# schematic.net
KiCad netlist of a schematic drawn in EasyEDA
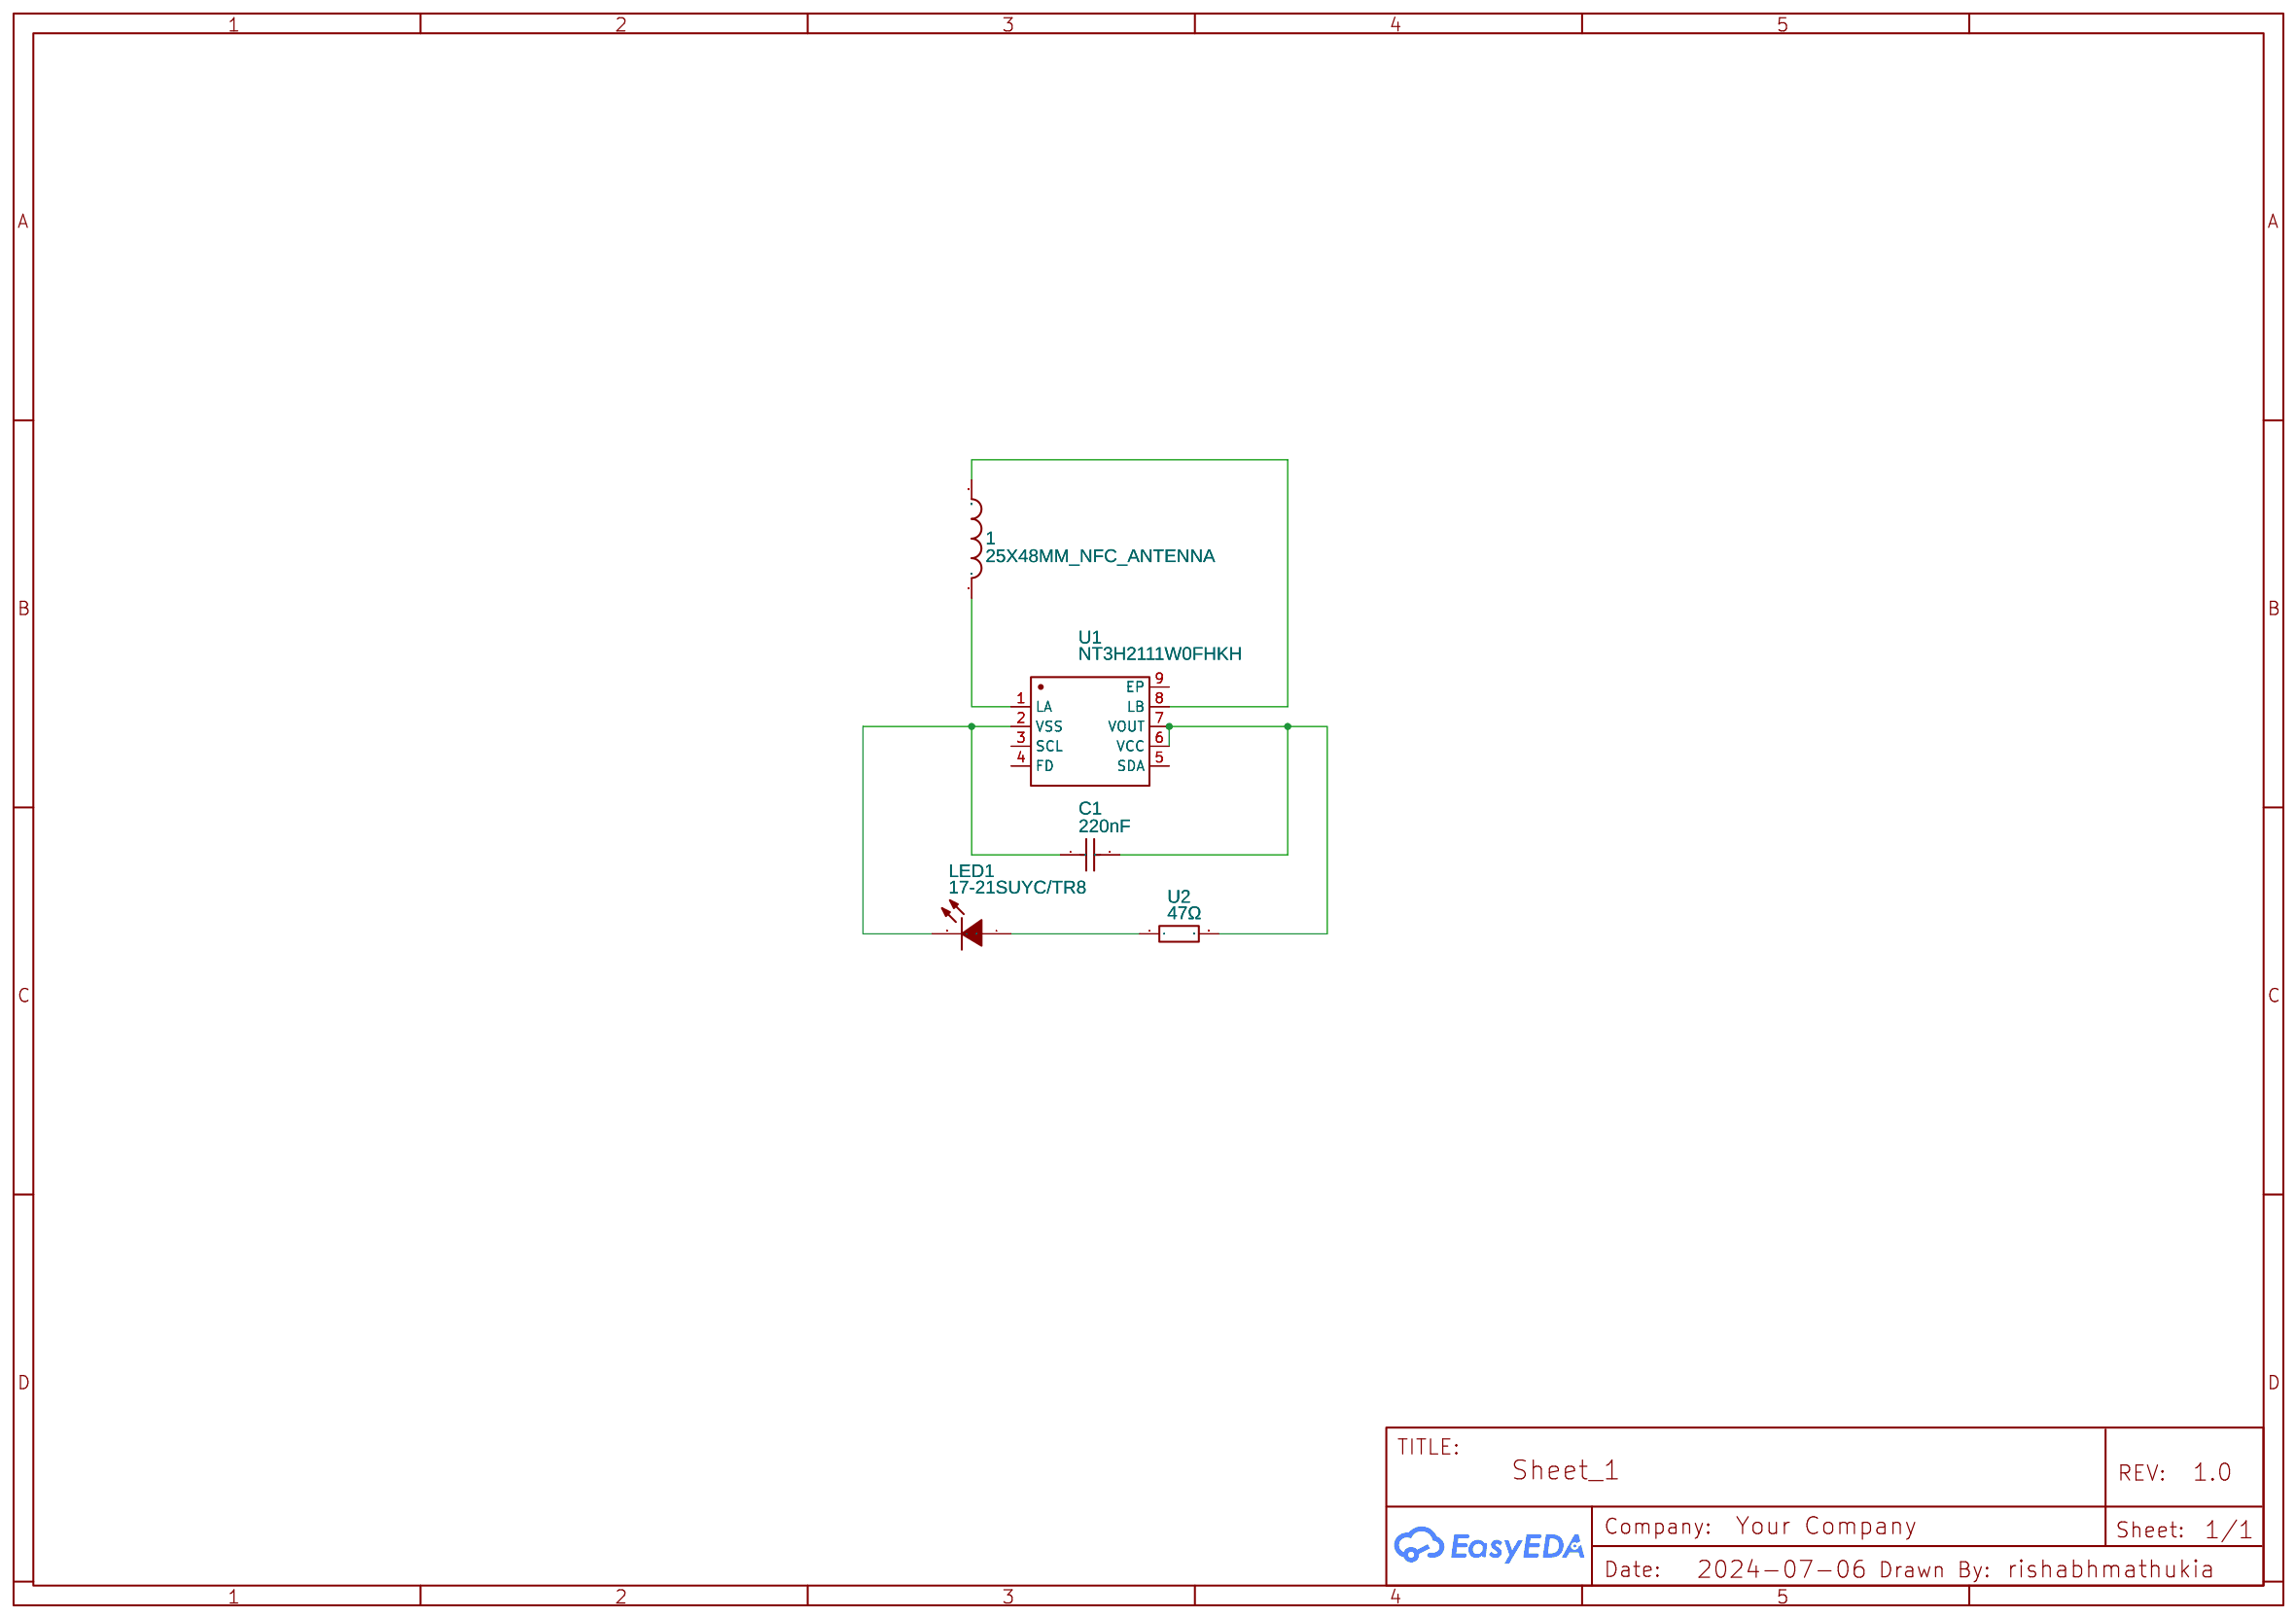
[diagram p0: schematic sheet]

(export (version "E")
  (design (tool "Eeschema 10.0.6"))
  (components
    (comp (ref "1") (value "25X48MM_NFC_ANTENNA") (libsource (lib "") (part "25X48MM_NFC_ANTENNA")))
    (comp (ref "C1")
      (value "220nF")
      (fields (field (name "Manufacturer Part") "C1005X5R0J224KT000F") (field (name "Manufacturer") "TDK"))
      (libsource (lib "") (part "C1005X5R0J224KT000F"))
    )
    (comp (ref "LED1")
      (value "17-21SUYC/TR8")
      (fields (field (name "Manufacturer Part") "KT-0805黄灯") (field (name "Manufacturer") "KENTO"))
      (libsource (lib "") (part "17-21SUYC/TR8"))
    )
    (comp (ref "U1")
      (value "NT3H2111W0FHKH")
      (fields (field (name "Manufacturer") "NXP(恩智浦)"))
      (libsource (lib "") (part "NT3H2111W0FHKH"))
    )
    (comp (ref "U2")
      (value "47Ω")
      (fields (field (name "Manufacturer Part") "MOF3WS-47Ω±5% T") (field (name "Manufacturer") "CCO(千志电子)"))
      (libsource (lib "") (part "MOF3WS-47Ω±5% T"))
    )
  )
  (nets
    (net (code "1") (name "Net-(LED1-+)") (class "Default")
      (node (ref "LED1") (pin "1") (pinfunction "+_1") (pintype "unspecified"))
      (node (ref "U2") (pin "1") (pinfunction "1_1") (pintype "unspecified"))
    )
    (net (code "2") (name "Net-(LED1--)") (class "Default")
      (node (ref "C1") (pin "1") (pinfunction "1_1") (pintype "input"))
      (node (ref "LED1") (pin "2") (pinfunction "-_2") (pintype "unspecified"))
      (node (ref "U1") (pin "2") (pinfunction "VSS_2") (pintype "unspecified"))
    )
    (net (code "3") (name "Net-(U1-LA)") (class "Default")
      (node (ref "1") (pin "P$2") (pinfunction "P$2_P$2") (pintype "bidirectional"))
      (node (ref "U1") (pin "1") (pinfunction "LA_1") (pintype "unspecified"))
    )
    (net (code "4") (name "Net-(U1-LB)") (class "Default")
      (node (ref "1") (pin "P$1") (pinfunction "P$1_P$1") (pintype "bidirectional"))
      (node (ref "U1") (pin "8") (pinfunction "LB_8") (pintype "unspecified"))
    )
    (net (code "5") (name "Net-(U1-VCC)") (class "Default")
      (node (ref "C1") (pin "2") (pinfunction "2_2") (pintype "input"))
      (node (ref "U1") (pin "6") (pinfunction "VCC_6") (pintype "unspecified"))
      (node (ref "U1") (pin "7") (pinfunction "VOUT_7") (pintype "unspecified"))
      (node (ref "U2") (pin "2") (pinfunction "2_2") (pintype "unspecified"))
    )
    (net (code "6") (name "unconnected-(U1-EP-Pad9)") (class "Default")
      (node (ref "U1") (pin "9") (pinfunction "EP_9") (pintype "unspecified"))
    )
    (net (code "7") (name "unconnected-(U1-FD-Pad4)") (class "Default")
      (node (ref "U1") (pin "4") (pinfunction "FD_4") (pintype "unspecified"))
    )
    (net (code "8") (name "unconnected-(U1-SCL-Pad3)") (class "Default")
      (node (ref "U1") (pin "3") (pinfunction "SCL_3") (pintype "unspecified"))
    )
    (net (code "9") (name "unconnected-(U1-SDA-Pad5)") (class "Default")
      (node (ref "U1") (pin "5") (pinfunction "SDA_5") (pintype "unspecified"))
    )
  )
)
